# NV_Sensor.net
KiCad netlist of a schematic drawn in EasyEDA Pro
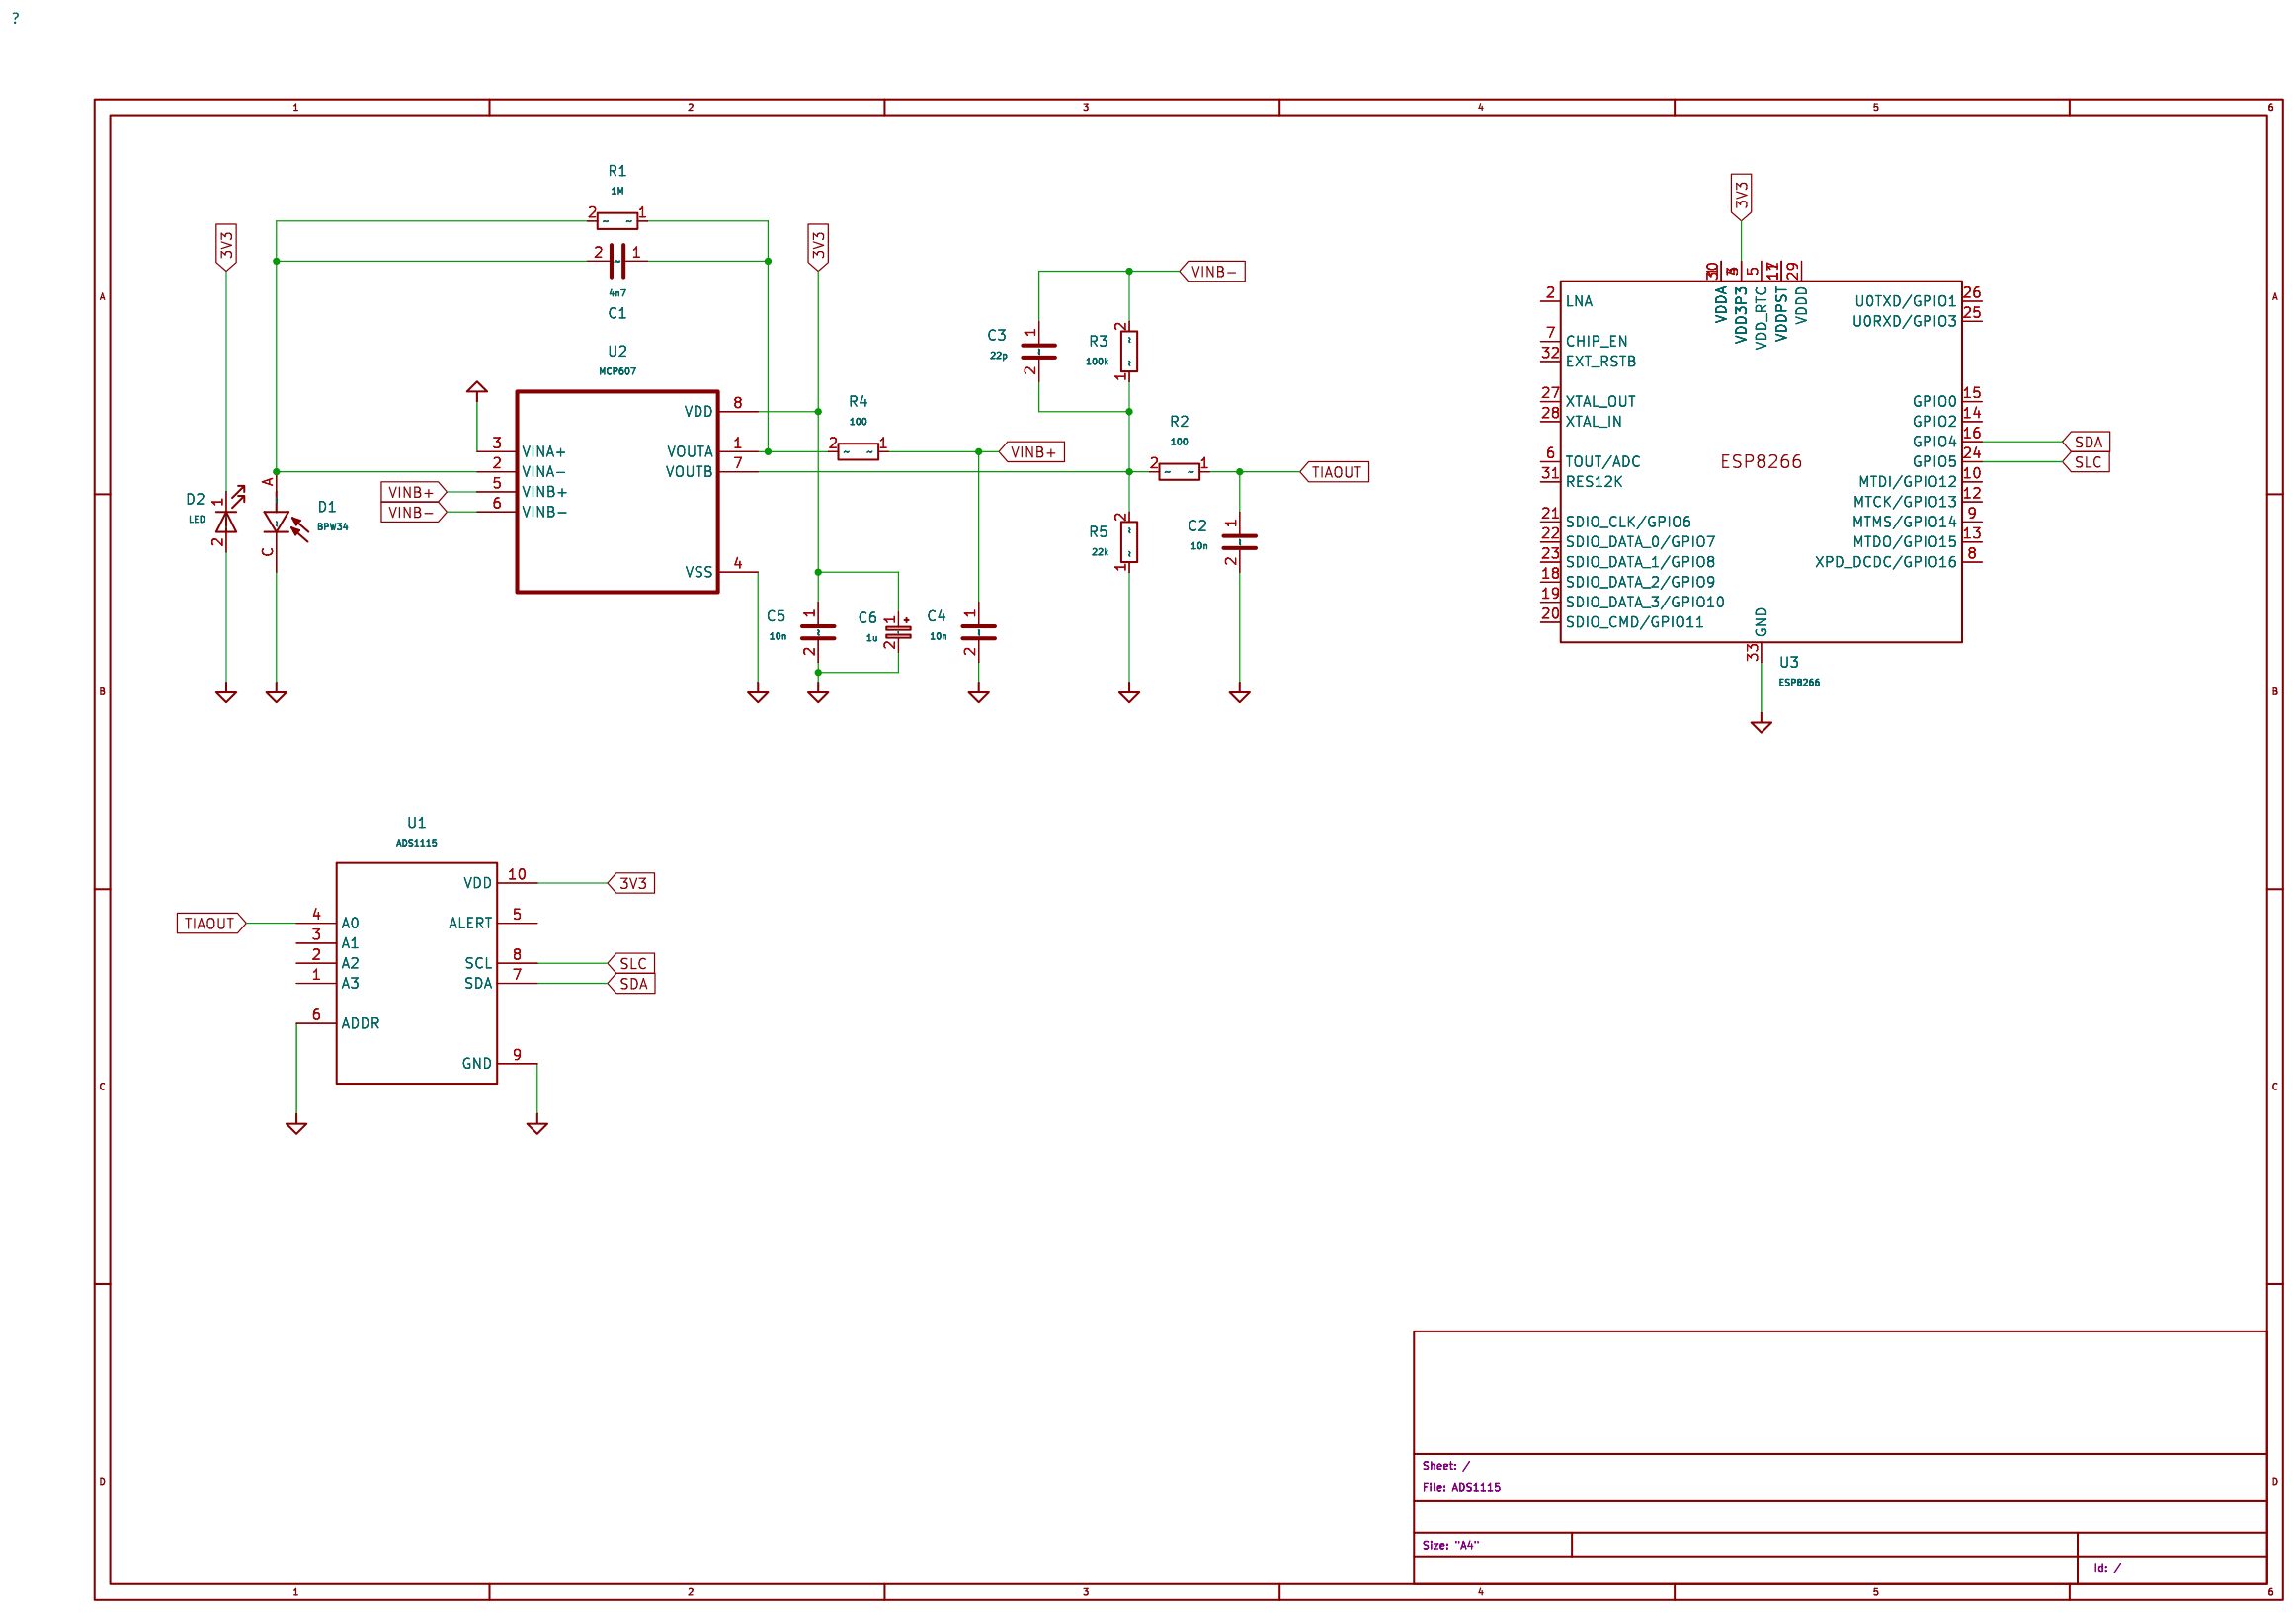
[diagram p0: schematic sheet]

(export (version "E")
  (design (tool "Eeschema 10.0.6"))
  (components
    (comp (ref "C1")
      (value "4n7")
      (description "Unpolarized capacitor")
      (libsource (lib "easyedapro") (part "Device_C"))
    )
    (comp (ref "C2")
      (value "10n")
      (description "Unpolarized capacitor")
      (libsource (lib "easyedapro") (part "Device_C"))
    )
    (comp (ref "C3")
      (value "22p")
      (description "Unpolarized capacitor")
      (libsource (lib "easyedapro") (part "Device_C"))
    )
    (comp (ref "C4")
      (value "10n")
      (description "Unpolarized capacitor")
      (libsource (lib "easyedapro") (part "Device_C"))
    )
    (comp (ref "C5")
      (value "10n")
      (description "Unpolarized capacitor")
      (libsource (lib "easyedapro") (part "Device_C"))
    )
    (comp (ref "C6")
      (value "1u")
      (description "Polarized capacitor, small symbol")
      (libsource (lib "easyedapro") (part "Device_C_Polarized_Small"))
    )
    (comp (ref "D1")
      (value "BPW34")
      (fields (field (name "MANUFACTURER") "Vishay") (field (name "MF") "Vishay Semiconductor"))
      (libsource (lib "easyedapro") (part "BPW34_BPW34"))
    )
    (comp (ref "D2")
      (value "LED")
      (description "Light emitting diode")
      (libsource (lib "easyedapro") (part "Device_LED"))
    )
    (comp (ref "R1") (value "1M") (description "Resistor") (libsource (lib "easyedapro") (part "Device_R")))
    (comp (ref "R2") (value "100") (description "Resistor") (libsource (lib "easyedapro") (part "Device_R")))
    (comp (ref "R3") (value "100k") (description "Resistor") (libsource (lib "easyedapro") (part "Device_R")))
    (comp (ref "R4") (value "100") (description "Resistor") (libsource (lib "easyedapro") (part "Device_R")))
    (comp (ref "R5") (value "22k") (description "Resistor") (libsource (lib "easyedapro") (part "Device_R")))
    (comp (ref "U1")
      (value "ADS1115")
      (fields (field (name "MANUFACTURER") "YKS") (field (name "MP") "ZC261500"))
      (libsource (lib "easyedapro") (part "ZC261500_ZC261500"))
    )
    (comp (ref "U2")
      (value "MCP607")
      (fields (field (name "MF") "Microchip") (field (name "MP") "MCP607-I/P"))
      (libsource (lib "easyedapro") (part "MCP607-I_P_MCP607-I_P"))
    )
    (comp (ref "U3") (value "ESP8266") (libsource (lib "easyedapro") (part "Espressif_ESP8266")))
  )
  (nets
    (net (code "1") (name "3V3") (class "Default")
      (node (ref "C5") (pin "1") (pinfunction "~_1") (pintype "unspecified"))
      (node (ref "C6") (pin "1") (pinfunction "~_1") (pintype "unspecified"))
      (node (ref "D2") (pin "1") (pinfunction "K_1") (pintype "unspecified"))
      (node (ref "U1") (pin "10") (pinfunction "VDD_10") (pintype "unspecified"))
      (node (ref "U2") (pin "8") (pinfunction "VDD_8") (pintype "unspecified"))
      (node (ref "U3") (pin "3") (pinfunction "VDD3P3_3") (pintype "unspecified"))
      (node (ref "U3") (pin "4") (pinfunction "VDD3P3_4") (pintype "unspecified"))
    )
    (net (code "2") (name "Net-(U2-VINA-)") (class "Default")
      (node (ref "C1") (pin "2") (pinfunction "~_2") (pintype "unspecified"))
      (node (ref "D1") (pin "A") (pinfunction "~_A") (pintype "unspecified"))
      (node (ref "R1") (pin "2") (pinfunction "~_2") (pintype "unspecified"))
      (node (ref "U2") (pin "2") (pinfunction "VINA-_2") (pintype "input"))
    )
    (net (code "3") (name "Net-(U2-VOUTA)") (class "Default")
      (node (ref "C1") (pin "1") (pinfunction "~_1") (pintype "unspecified"))
      (node (ref "R1") (pin "1") (pinfunction "~_1") (pintype "unspecified"))
      (node (ref "R4") (pin "2") (pinfunction "~_2") (pintype "unspecified"))
      (node (ref "U2") (pin "1") (pinfunction "VOUTA_1") (pintype "output"))
    )
    (net (code "4") (name "Net-(U2-VOUTB)") (class "Default")
      (node (ref "C3") (pin "2") (pinfunction "~_2") (pintype "unspecified"))
      (node (ref "R2") (pin "2") (pinfunction "~_2") (pintype "unspecified"))
      (node (ref "R3") (pin "1") (pinfunction "~_1") (pintype "unspecified"))
      (node (ref "R5") (pin "2") (pinfunction "~_2") (pintype "unspecified"))
      (node (ref "U2") (pin "7") (pinfunction "VOUTB_7") (pintype "output"))
    )
    (net (code "5") (name "Net-(U3-VDDA-Pad1)") (class "Default")
      (node (ref "U3") (pin "1") (pinfunction "VDDA_1") (pintype "unspecified"))
      (node (ref "U3") (pin "30") (pinfunction "VDDA_30") (pintype "unspecified"))
    )
    (net (code "6") (name "Net-(U3-VDDPST-Pad11)") (class "Default")
      (node (ref "U3") (pin "11") (pinfunction "VDDPST_11") (pintype "unspecified"))
      (node (ref "U3") (pin "17") (pinfunction "VDDPST_17") (pintype "unspecified"))
    )
    (net (code "7") (name "POWER_GND") (class "Default")
      (node (ref "C2") (pin "2") (pinfunction "~_2") (pintype "unspecified"))
      (node (ref "C4") (pin "2") (pinfunction "~_2") (pintype "unspecified"))
      (node (ref "C5") (pin "2") (pinfunction "~_2") (pintype "unspecified"))
      (node (ref "C6") (pin "2") (pinfunction "~_2") (pintype "unspecified"))
      (node (ref "D1") (pin "C") (pinfunction "~_C") (pintype "unspecified"))
      (node (ref "D2") (pin "2") (pinfunction "A_2") (pintype "unspecified"))
      (node (ref "R5") (pin "1") (pinfunction "~_1") (pintype "unspecified"))
      (node (ref "U1") (pin "6") (pinfunction "ADDR_6") (pintype "input"))
      (node (ref "U1") (pin "9") (pinfunction "GND_9") (pintype "unspecified"))
      (node (ref "U2") (pin "3") (pinfunction "VINA+_3") (pintype "input"))
      (node (ref "U2") (pin "4") (pinfunction "VSS_4") (pintype "unspecified"))
      (node (ref "U3") (pin "33") (pinfunction "GND_33") (pintype "unspecified"))
    )
    (net (code "8") (name "SDA") (class "Default")
      (node (ref "U1") (pin "7") (pinfunction "SDA_7") (pintype "bidirectional"))
      (node (ref "U3") (pin "16") (pinfunction "GPIO4_16") (pintype "bidirectional"))
    )
    (net (code "9") (name "SLC") (class "Default")
      (node (ref "U1") (pin "8") (pinfunction "SCL_8") (pintype "input"))
      (node (ref "U3") (pin "24") (pinfunction "GPIO5_24") (pintype "bidirectional"))
    )
    (net (code "10") (name "TIAOUT") (class "Default")
      (node (ref "C2") (pin "1") (pinfunction "~_1") (pintype "unspecified"))
      (node (ref "R2") (pin "1") (pinfunction "~_1") (pintype "unspecified"))
      (node (ref "U1") (pin "4") (pinfunction "A0_4") (pintype "input"))
    )
    (net (code "11") (name "VINB+") (class "Default")
      (node (ref "C4") (pin "1") (pinfunction "~_1") (pintype "unspecified"))
      (node (ref "R4") (pin "1") (pinfunction "~_1") (pintype "unspecified"))
      (node (ref "U2") (pin "5") (pinfunction "VINB+_5") (pintype "input"))
    )
    (net (code "12") (name "VINB-") (class "Default")
      (node (ref "C3") (pin "1") (pinfunction "~_1") (pintype "unspecified"))
      (node (ref "R3") (pin "2") (pinfunction "~_2") (pintype "unspecified"))
      (node (ref "U2") (pin "6") (pinfunction "VINB-_6") (pintype "input"))
    )
    (net (code "13") (name "unconnected-(U1-A1-Pad3)") (class "Default")
      (node (ref "U1") (pin "3") (pinfunction "A1_3") (pintype "input"))
    )
    (net (code "14") (name "unconnected-(U1-A2-Pad2)") (class "Default")
      (node (ref "U1") (pin "2") (pinfunction "A2_2") (pintype "input"))
    )
    (net (code "15") (name "unconnected-(U1-A3-Pad1)") (class "Default")
      (node (ref "U1") (pin "1") (pinfunction "A3_1") (pintype "input"))
    )
    (net (code "16") (name "unconnected-(U1-ALERT-Pad5)") (class "Default")
      (node (ref "U1") (pin "5") (pinfunction "ALERT_5") (pintype "bidirectional"))
    )
    (net (code "17") (name "unconnected-(U3-CHIP_EN-Pad7)") (class "Default")
      (node (ref "U3") (pin "7") (pinfunction "CHIP_EN_7") (pintype "input"))
    )
    (net (code "18") (name "unconnected-(U3-EXT_RSTB-Pad32)") (class "Default")
      (node (ref "U3") (pin "32") (pinfunction "EXT_RSTB_32") (pintype "unspecified"))
    )
    (net (code "19") (name "unconnected-(U3-GPIO0-Pad15)") (class "Default")
      (node (ref "U3") (pin "15") (pinfunction "GPIO0_15") (pintype "bidirectional"))
    )
    (net (code "20") (name "unconnected-(U3-GPIO2-Pad14)") (class "Default")
      (node (ref "U3") (pin "14") (pinfunction "GPIO2_14") (pintype "bidirectional"))
    )
    (net (code "21") (name "unconnected-(U3-LNA-Pad2)") (class "Default")
      (node (ref "U3") (pin "2") (pinfunction "LNA_2") (pintype "unspecified"))
    )
    (net (code "22") (name "unconnected-(U3-MTCK{slash}GPIO13-Pad12)") (class "Default")
      (node (ref "U3") (pin "12") (pinfunction "MTCK/GPIO13_12") (pintype "bidirectional"))
    )
    (net (code "23") (name "unconnected-(U3-MTDI{slash}GPIO12-Pad10)") (class "Default")
      (node (ref "U3") (pin "10") (pinfunction "MTDI/GPIO12_10") (pintype "bidirectional"))
    )
    (net (code "24") (name "unconnected-(U3-MTDO{slash}GPIO15-Pad13)") (class "Default")
      (node (ref "U3") (pin "13") (pinfunction "MTDO/GPIO15_13") (pintype "bidirectional"))
    )
    (net (code "25") (name "unconnected-(U3-MTMS{slash}GPIO14-Pad9)") (class "Default")
      (node (ref "U3") (pin "9") (pinfunction "MTMS/GPIO14_9") (pintype "bidirectional"))
    )
    (net (code "26") (name "unconnected-(U3-RES12K-Pad31)") (class "Default")
      (node (ref "U3") (pin "31") (pinfunction "RES12K_31") (pintype "input"))
    )
    (net (code "27") (name "unconnected-(U3-SDIO_CLK{slash}GPIO6-Pad21)") (class "Default")
      (node (ref "U3") (pin "21") (pinfunction "SDIO_CLK/GPIO6_21") (pintype "bidirectional"))
    )
    (net (code "28") (name "unconnected-(U3-SDIO_CMD{slash}GPIO11-Pad20)") (class "Default")
      (node (ref "U3") (pin "20") (pinfunction "SDIO_CMD/GPIO11_20") (pintype "bidirectional"))
    )
    (net (code "29") (name "unconnected-(U3-SDIO_DATA_0{slash}GPIO7-Pad22)") (class "Default")
      (node (ref "U3") (pin "22") (pinfunction "SDIO_DATA_0/GPIO7_22") (pintype "bidirectional"))
    )
    (net (code "30") (name "unconnected-(U3-SDIO_DATA_1{slash}GPIO8-Pad23)") (class "Default")
      (node (ref "U3") (pin "23") (pinfunction "SDIO_DATA_1/GPIO8_23") (pintype "bidirectional"))
    )
    (net (code "31") (name "unconnected-(U3-SDIO_DATA_2{slash}GPIO9-Pad18)") (class "Default")
      (node (ref "U3") (pin "18") (pinfunction "SDIO_DATA_2/GPIO9_18") (pintype "bidirectional"))
    )
    (net (code "32") (name "unconnected-(U3-SDIO_DATA_3{slash}GPIO10-Pad19)") (class "Default")
      (node (ref "U3") (pin "19") (pinfunction "SDIO_DATA_3/GPIO10_19") (pintype "bidirectional"))
    )
    (net (code "33") (name "unconnected-(U3-TOUT{slash}ADC-Pad6)") (class "Default")
      (node (ref "U3") (pin "6") (pinfunction "TOUT/ADC_6") (pintype "input"))
    )
    (net (code "34") (name "unconnected-(U3-U0RXD{slash}GPIO3-Pad25)") (class "Default")
      (node (ref "U3") (pin "25") (pinfunction "U0RXD/GPIO3_25") (pintype "bidirectional"))
    )
    (net (code "35") (name "unconnected-(U3-U0TXD{slash}GPIO1-Pad26)") (class "Default")
      (node (ref "U3") (pin "26") (pinfunction "U0TXD/GPIO1_26") (pintype "bidirectional"))
    )
    (net (code "36") (name "unconnected-(U3-VDDD-Pad29)") (class "Default")
      (node (ref "U3") (pin "29") (pinfunction "VDDD_29") (pintype "unspecified"))
    )
    (net (code "37") (name "unconnected-(U3-VDD_RTC-Pad5)") (class "Default")
      (node (ref "U3") (pin "5") (pinfunction "VDD_RTC_5") (pintype "unspecified"))
    )
    (net (code "38") (name "unconnected-(U3-XPD_DCDC{slash}GPIO16-Pad8)") (class "Default")
      (node (ref "U3") (pin "8") (pinfunction "XPD_DCDC/GPIO16_8") (pintype "bidirectional"))
    )
    (net (code "39") (name "unconnected-(U3-XTAL_IN-Pad28)") (class "Default")
      (node (ref "U3") (pin "28") (pinfunction "XTAL_IN_28") (pintype "bidirectional"))
    )
    (net (code "40") (name "unconnected-(U3-XTAL_OUT-Pad27)") (class "Default")
      (node (ref "U3") (pin "27") (pinfunction "XTAL_OUT_27") (pintype "bidirectional"))
    )
  )
)
